# multiplexor_circuit.net
KiCad netlist of a schematic drawn in Altium Designer
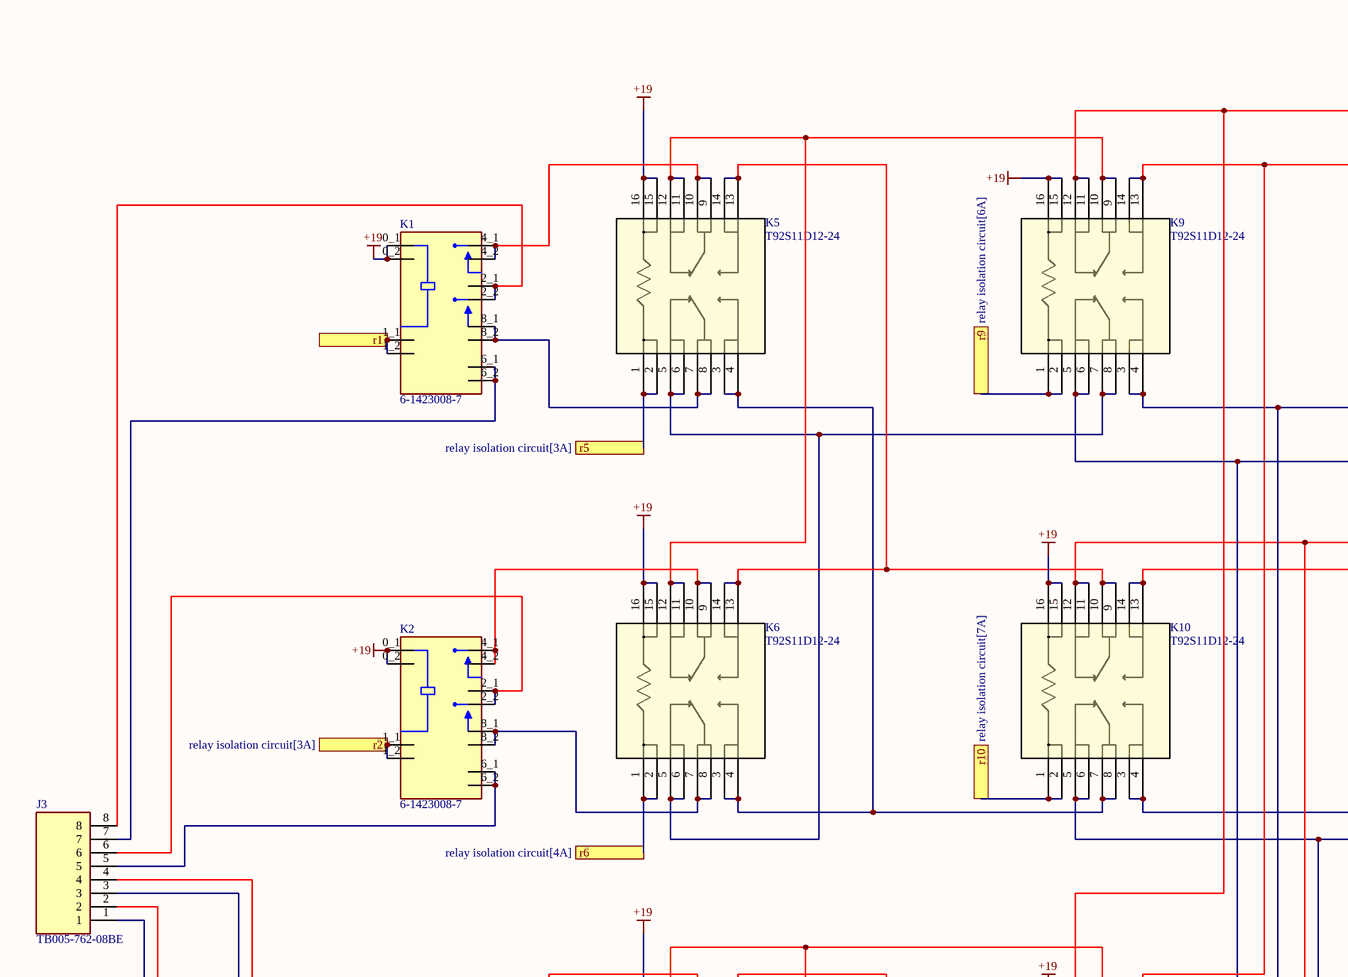
[diagram p0: multiplexor circuit.SchDoc, top left]
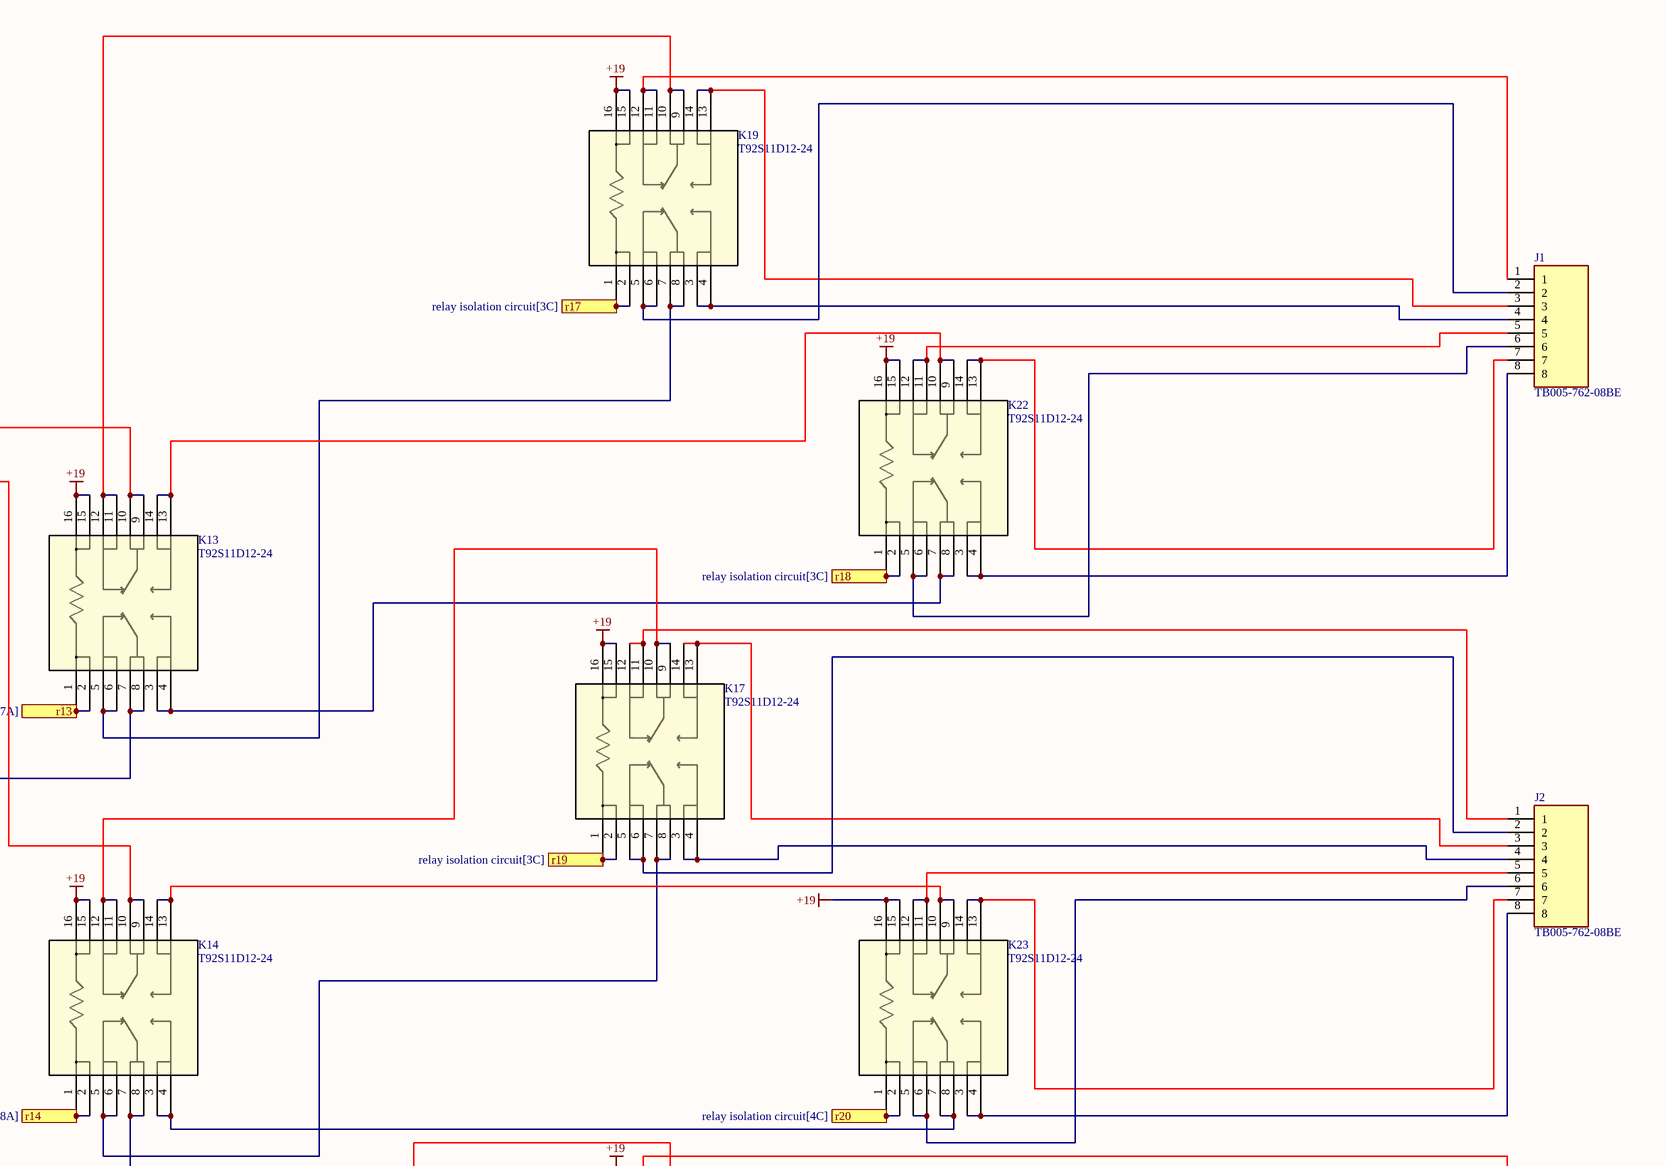
[diagram p1: multiplexor circuit.SchDoc, top right]
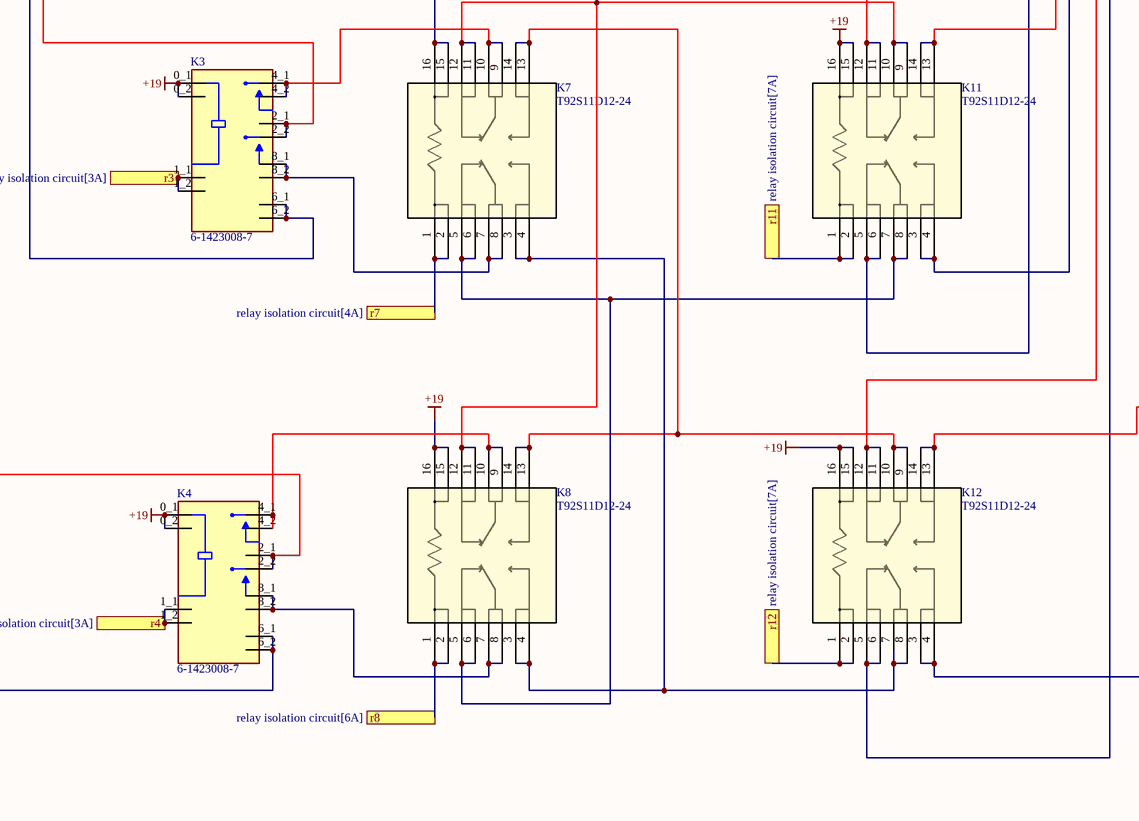
[diagram p2: multiplexor circuit.SchDoc, bottom left]
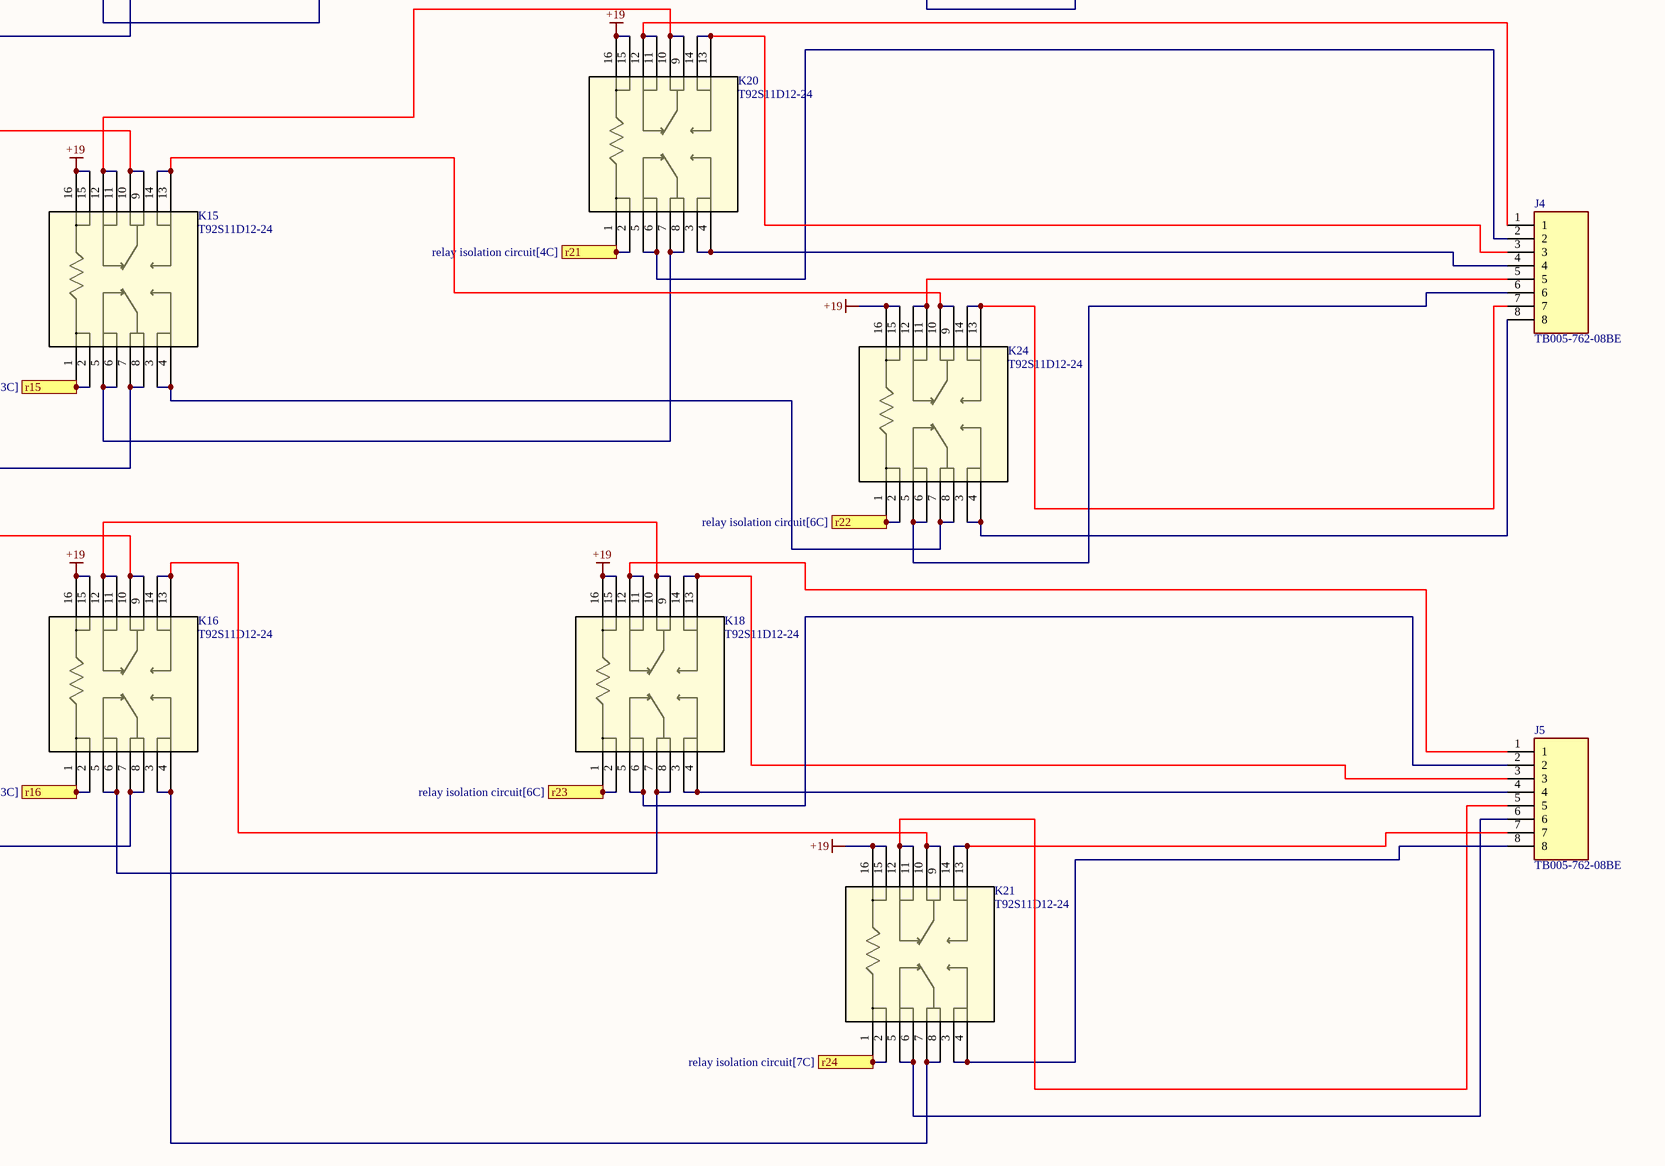
[diagram p3: multiplexor circuit.SchDoc, bottom right]

(export (version "E")
  (design (tool "Eeschema 10.0.6"))
  (components
    (comp (ref "J1")
      (value "TB005-762-08BE")
      (footprint "CUI_TB005-762-08BE")
      (libsource (lib "TB005-762-08BE") (part "TB005-762-08BE"))
    )
    (comp (ref "J2")
      (value "TB005-762-08BE")
      (footprint "CUI_TB005-762-08BE")
      (libsource (lib "TB005-762-08BE") (part "TB005-762-08BE"))
    )
    (comp (ref "J3")
      (value "TB005-762-08BE")
      (footprint "CUI_TB005-762-08BE")
      (libsource (lib "") (part "TB005-762-08BE_1"))
    )
    (comp (ref "J4")
      (value "TB005-762-08BE")
      (footprint "CUI_TB005-762-08BE")
      (libsource (lib "TB005-762-08BE") (part "TB005-762-08BE"))
    )
    (comp (ref "J5")
      (value "TB005-762-08BE")
      (footprint "CUI_TB005-762-08BE")
      (libsource (lib "TB005-762-08BE") (part "TB005-762-08BE"))
    )
    (comp (ref "K1")
      (value "6-1423008-7")
      (footprint "RELAY_6-1423008-7")
      (description "General Purpose Relay DPST-NO (2 Form A) 24VDC Coil Through Hole")
      (fields (field (name "MF") "TE Connectivity / P&B"))
      (libsource (lib "6-1423008-7") (part "6-1423008-7"))
    )
    (comp (ref "K2")
      (value "6-1423008-7")
      (footprint "RELAY_6-1423008-7")
      (description "General Purpose Relay DPST-NO (2 Form A) 24VDC Coil Through Hole")
      (fields (field (name "MF") "TE Connectivity / P&B"))
      (libsource (lib "6-1423008-7") (part "6-1423008-7"))
    )
    (comp (ref "K3")
      (value "6-1423008-7")
      (footprint "RELAY_6-1423008-7")
      (description "General Purpose Relay DPST-NO (2 Form A) 24VDC Coil Through Hole")
      (fields (field (name "MF") "TE Connectivity / P&B"))
      (libsource (lib "6-1423008-7") (part "6-1423008-7"))
    )
    (comp (ref "K4")
      (value "6-1423008-7")
      (footprint "RELAY_6-1423008-7")
      (description "General Purpose Relay DPST-NO (2 Form A) 24VDC Coil Through Hole")
      (fields (field (name "MF") "TE Connectivity / P&B"))
      (libsource (lib "6-1423008-7") (part "6-1423008-7"))
    )
    (comp (ref "K5")
      (value "T92S11D12-24")
      (footprint "T92S11D12-24_TEC-corrected")
      (description "No Description Available")
      (fields (field (name "COPYRIGHT") "Copyright (C) 2022 Ultra Librarian. All rights reserved."))
      (libsource (lib "multiplexorparts") (part "T92S11D12-24"))
    )
    (comp (ref "K6")
      (value "T92S11D12-24")
      (footprint "T92S11D12-24_TEC-corrected")
      (description "No Description Available")
      (fields (field (name "COPYRIGHT") "Copyright (C) 2022 Ultra Librarian. All rights reserved."))
      (libsource (lib "multiplexorparts") (part "T92S11D12-24"))
    )
    (comp (ref "K7")
      (value "T92S11D12-24")
      (footprint "T92S11D12-24_TEC-corrected")
      (description "No Description Available")
      (fields (field (name "COPYRIGHT") "Copyright (C) 2022 Ultra Librarian. All rights reserved."))
      (libsource (lib "multiplexorparts") (part "T92S11D12-24"))
    )
    (comp (ref "K8")
      (value "T92S11D12-24")
      (footprint "T92S11D12-24_TEC-corrected")
      (description "No Description Available")
      (fields (field (name "COPYRIGHT") "Copyright (C) 2022 Ultra Librarian. All rights reserved."))
      (libsource (lib "multiplexorparts") (part "T92S11D12-24"))
    )
    (comp (ref "K9")
      (value "T92S11D12-24")
      (footprint "T92S11D12-24_TEC-corrected")
      (description "No Description Available")
      (fields (field (name "COPYRIGHT") "Copyright (C) 2022 Ultra Librarian. All rights reserved."))
      (libsource (lib "multiplexorparts") (part "T92S11D12-24"))
    )
    (comp (ref "K10")
      (value "T92S11D12-24")
      (footprint "T92S11D12-24_TEC-corrected")
      (description "No Description Available")
      (fields (field (name "COPYRIGHT") "Copyright (C) 2022 Ultra Librarian. All rights reserved."))
      (libsource (lib "multiplexorparts") (part "T92S11D12-24"))
    )
    (comp (ref "K11")
      (value "T92S11D12-24")
      (footprint "T92S11D12-24_TEC-corrected")
      (description "No Description Available")
      (fields (field (name "COPYRIGHT") "Copyright (C) 2022 Ultra Librarian. All rights reserved."))
      (libsource (lib "multiplexorparts") (part "T92S11D12-24"))
    )
    (comp (ref "K12")
      (value "T92S11D12-24")
      (footprint "T92S11D12-24_TEC-corrected")
      (description "No Description Available")
      (fields (field (name "COPYRIGHT") "Copyright (C) 2022 Ultra Librarian. All rights reserved."))
      (libsource (lib "multiplexorparts") (part "T92S11D12-24"))
    )
    (comp (ref "K13")
      (value "T92S11D12-24")
      (footprint "T92S11D12-24_TEC-corrected")
      (description "No Description Available")
      (fields (field (name "COPYRIGHT") "Copyright (C) 2022 Ultra Librarian. All rights reserved."))
      (libsource (lib "multiplexorparts") (part "T92S11D12-24"))
    )
    (comp (ref "K14")
      (value "T92S11D12-24")
      (footprint "T92S11D12-24_TEC-corrected")
      (description "No Description Available")
      (fields (field (name "COPYRIGHT") "Copyright (C) 2022 Ultra Librarian. All rights reserved."))
      (libsource (lib "multiplexorparts") (part "T92S11D12-24"))
    )
    (comp (ref "K15")
      (value "T92S11D12-24")
      (footprint "T92S11D12-24_TEC-corrected")
      (description "No Description Available")
      (fields (field (name "COPYRIGHT") "Copyright (C) 2022 Ultra Librarian. All rights reserved."))
      (libsource (lib "multiplexorparts") (part "T92S11D12-24"))
    )
    (comp (ref "K16")
      (value "T92S11D12-24")
      (footprint "T92S11D12-24_TEC-corrected")
      (description "No Description Available")
      (fields (field (name "COPYRIGHT") "Copyright (C) 2022 Ultra Librarian. All rights reserved."))
      (libsource (lib "multiplexorparts") (part "T92S11D12-24"))
    )
    (comp (ref "K17")
      (value "T92S11D12-24")
      (footprint "T92S11D12-24_TEC-corrected")
      (description "No Description Available")
      (fields (field (name "COPYRIGHT") "Copyright (C) 2022 Ultra Librarian. All rights reserved."))
      (libsource (lib "multiplexorparts") (part "T92S11D12-24"))
    )
    (comp (ref "K18")
      (value "T92S11D12-24")
      (footprint "T92S11D12-24_TEC-corrected")
      (description "No Description Available")
      (fields (field (name "COPYRIGHT") "Copyright (C) 2022 Ultra Librarian. All rights reserved."))
      (libsource (lib "multiplexorparts") (part "T92S11D12-24"))
    )
    (comp (ref "K19")
      (value "T92S11D12-24")
      (footprint "T92S11D12-24_TEC-corrected")
      (description "No Description Available")
      (fields (field (name "COPYRIGHT") "Copyright (C) 2022 Ultra Librarian. All rights reserved."))
      (libsource (lib "multiplexorparts") (part "T92S11D12-24"))
    )
    (comp (ref "K20")
      (value "T92S11D12-24")
      (footprint "T92S11D12-24_TEC-corrected")
      (description "No Description Available")
      (fields (field (name "COPYRIGHT") "Copyright (C) 2022 Ultra Librarian. All rights reserved."))
      (libsource (lib "multiplexorparts") (part "T92S11D12-24"))
    )
    (comp (ref "K21")
      (value "T92S11D12-24")
      (footprint "T92S11D12-24_TEC-corrected")
      (description "No Description Available")
      (fields (field (name "COPYRIGHT") "Copyright (C) 2022 Ultra Librarian. All rights reserved."))
      (libsource (lib "multiplexorparts") (part "T92S11D12-24"))
    )
    (comp (ref "K22")
      (value "T92S11D12-24")
      (footprint "T92S11D12-24_TEC-corrected")
      (description "No Description Available")
      (fields (field (name "COPYRIGHT") "Copyright (C) 2022 Ultra Librarian. All rights reserved."))
      (libsource (lib "multiplexorparts") (part "T92S11D12-24"))
    )
    (comp (ref "K23")
      (value "T92S11D12-24")
      (footprint "T92S11D12-24_TEC-corrected")
      (description "No Description Available")
      (fields (field (name "COPYRIGHT") "Copyright (C) 2022 Ultra Librarian. All rights reserved."))
      (libsource (lib "multiplexorparts") (part "T92S11D12-24"))
    )
    (comp (ref "K24")
      (value "T92S11D12-24")
      (footprint "T92S11D12-24_TEC-corrected")
      (description "No Description Available")
      (fields (field (name "COPYRIGHT") "Copyright (C) 2022 Ultra Librarian. All rights reserved."))
      (libsource (lib "multiplexorparts") (part "T92S11D12-24"))
    )
  )
  (nets
    (net (code "1") (name "+19") (class "Default")
      (node (ref "K1") (pin "0_1") (pinfunction "COIL1_0_1") (pintype "passive"))
      (node (ref "K1") (pin "0_2") (pinfunction "COIL1_0_2") (pintype "passive"))
      (node (ref "K10") (pin "15") (pinfunction "15_15") (pintype "passive"))
      (node (ref "K10") (pin "16") (pinfunction "16_16") (pintype "passive"))
      (node (ref "K11") (pin "15") (pinfunction "15_15") (pintype "passive"))
      (node (ref "K11") (pin "16") (pinfunction "16_16") (pintype "passive"))
      (node (ref "K12") (pin "15") (pinfunction "15_15") (pintype "passive"))
      (node (ref "K12") (pin "16") (pinfunction "16_16") (pintype "passive"))
      (node (ref "K13") (pin "15") (pinfunction "15_15") (pintype "passive"))
      (node (ref "K13") (pin "16") (pinfunction "16_16") (pintype "passive"))
      (node (ref "K14") (pin "15") (pinfunction "15_15") (pintype "passive"))
      (node (ref "K14") (pin "16") (pinfunction "16_16") (pintype "passive"))
      (node (ref "K15") (pin "15") (pinfunction "15_15") (pintype "passive"))
      (node (ref "K15") (pin "16") (pinfunction "16_16") (pintype "passive"))
      (node (ref "K16") (pin "15") (pinfunction "15_15") (pintype "passive"))
      (node (ref "K16") (pin "16") (pinfunction "16_16") (pintype "passive"))
      (node (ref "K17") (pin "15") (pinfunction "15_15") (pintype "passive"))
      (node (ref "K17") (pin "16") (pinfunction "16_16") (pintype "passive"))
      (node (ref "K18") (pin "15") (pinfunction "15_15") (pintype "passive"))
      (node (ref "K18") (pin "16") (pinfunction "16_16") (pintype "passive"))
      (node (ref "K19") (pin "15") (pinfunction "15_15") (pintype "passive"))
      (node (ref "K19") (pin "16") (pinfunction "16_16") (pintype "passive"))
      (node (ref "K2") (pin "0_1") (pinfunction "COIL1_0_1") (pintype "passive"))
      (node (ref "K2") (pin "0_2") (pinfunction "COIL1_0_2") (pintype "passive"))
      (node (ref "K20") (pin "15") (pinfunction "15_15") (pintype "passive"))
      (node (ref "K20") (pin "16") (pinfunction "16_16") (pintype "passive"))
      (node (ref "K21") (pin "15") (pinfunction "15_15") (pintype "passive"))
      (node (ref "K21") (pin "16") (pinfunction "16_16") (pintype "passive"))
      (node (ref "K22") (pin "15") (pinfunction "15_15") (pintype "passive"))
      (node (ref "K22") (pin "16") (pinfunction "16_16") (pintype "passive"))
      (node (ref "K23") (pin "15") (pinfunction "15_15") (pintype "passive"))
      (node (ref "K23") (pin "16") (pinfunction "16_16") (pintype "passive"))
      (node (ref "K24") (pin "15") (pinfunction "15_15") (pintype "passive"))
      (node (ref "K24") (pin "16") (pinfunction "16_16") (pintype "passive"))
      (node (ref "K3") (pin "0_1") (pinfunction "COIL1_0_1") (pintype "passive"))
      (node (ref "K3") (pin "0_2") (pinfunction "COIL1_0_2") (pintype "passive"))
      (node (ref "K4") (pin "0_1") (pinfunction "COIL1_0_1") (pintype "passive"))
      (node (ref "K4") (pin "0_2") (pinfunction "COIL1_0_2") (pintype "passive"))
      (node (ref "K5") (pin "15") (pinfunction "15_15") (pintype "passive"))
      (node (ref "K5") (pin "16") (pinfunction "16_16") (pintype "passive"))
      (node (ref "K6") (pin "15") (pinfunction "15_15") (pintype "passive"))
      (node (ref "K6") (pin "16") (pinfunction "16_16") (pintype "passive"))
      (node (ref "K7") (pin "15") (pinfunction "15_15") (pintype "passive"))
      (node (ref "K7") (pin "16") (pinfunction "16_16") (pintype "passive"))
      (node (ref "K8") (pin "15") (pinfunction "15_15") (pintype "passive"))
      (node (ref "K8") (pin "16") (pinfunction "16_16") (pintype "passive"))
      (node (ref "K9") (pin "15") (pinfunction "15_15") (pintype "passive"))
      (node (ref "K9") (pin "16") (pinfunction "16_16") (pintype "passive"))
    )
    (net (code "2") (name "/r1") (class "Default")
      (node (ref "K1") (pin "1_1") (pinfunction "COIL2_1_1") (pintype "passive"))
      (node (ref "K1") (pin "1_2") (pinfunction "COIL2_1_2") (pintype "passive"))
    )
    (net (code "3") (name "/r2") (class "Default")
      (node (ref "K2") (pin "1_1") (pinfunction "COIL2_1_1") (pintype "passive"))
      (node (ref "K2") (pin "1_2") (pinfunction "COIL2_1_2") (pintype "passive"))
    )
    (net (code "4") (name "/r3") (class "Default")
      (node (ref "K3") (pin "1_1") (pinfunction "COIL2_1_1") (pintype "passive"))
      (node (ref "K3") (pin "1_2") (pinfunction "COIL2_1_2") (pintype "passive"))
    )
    (net (code "5") (name "/r4") (class "Default")
      (node (ref "K4") (pin "1_1") (pinfunction "COIL2_1_1") (pintype "passive"))
      (node (ref "K4") (pin "1_2") (pinfunction "COIL2_1_2") (pintype "passive"))
    )
    (net (code "6") (name "/r5") (class "Default")
      (node (ref "K5") (pin "1") (pinfunction "1_1") (pintype "passive"))
      (node (ref "K5") (pin "2") (pinfunction "2_2") (pintype "passive"))
    )
    (net (code "7") (name "/r6") (class "Default")
      (node (ref "K6") (pin "1") (pinfunction "1_1") (pintype "passive"))
      (node (ref "K6") (pin "2") (pinfunction "2_2") (pintype "passive"))
    )
    (net (code "8") (name "/r7") (class "Default")
      (node (ref "K7") (pin "1") (pinfunction "1_1") (pintype "passive"))
      (node (ref "K7") (pin "2") (pinfunction "2_2") (pintype "passive"))
    )
    (net (code "9") (name "/r8") (class "Default")
      (node (ref "K8") (pin "1") (pinfunction "1_1") (pintype "passive"))
      (node (ref "K8") (pin "2") (pinfunction "2_2") (pintype "passive"))
    )
    (net (code "10") (name "/r9") (class "Default")
      (node (ref "K9") (pin "1") (pinfunction "1_1") (pintype "passive"))
      (node (ref "K9") (pin "2") (pinfunction "2_2") (pintype "passive"))
    )
    (net (code "11") (name "/r10") (class "Default")
      (node (ref "K10") (pin "1") (pinfunction "1_1") (pintype "passive"))
      (node (ref "K10") (pin "2") (pinfunction "2_2") (pintype "passive"))
    )
    (net (code "12") (name "/r11") (class "Default")
      (node (ref "K11") (pin "1") (pinfunction "1_1") (pintype "passive"))
      (node (ref "K11") (pin "2") (pinfunction "2_2") (pintype "passive"))
    )
    (net (code "13") (name "/r12") (class "Default")
      (node (ref "K12") (pin "1") (pinfunction "1_1") (pintype "passive"))
      (node (ref "K12") (pin "2") (pinfunction "2_2") (pintype "passive"))
    )
    (net (code "14") (name "/r13") (class "Default")
      (node (ref "K13") (pin "1") (pinfunction "1_1") (pintype "passive"))
      (node (ref "K13") (pin "2") (pinfunction "2_2") (pintype "passive"))
    )
    (net (code "15") (name "/r14") (class "Default")
      (node (ref "K14") (pin "1") (pinfunction "1_1") (pintype "passive"))
      (node (ref "K14") (pin "2") (pinfunction "2_2") (pintype "passive"))
    )
    (net (code "16") (name "/r15") (class "Default")
      (node (ref "K15") (pin "1") (pinfunction "1_1") (pintype "passive"))
      (node (ref "K15") (pin "2") (pinfunction "2_2") (pintype "passive"))
    )
    (net (code "17") (name "/r16") (class "Default")
      (node (ref "K16") (pin "1") (pinfunction "1_1") (pintype "passive"))
      (node (ref "K16") (pin "2") (pinfunction "2_2") (pintype "passive"))
    )
    (net (code "18") (name "/r17") (class "Default")
      (node (ref "K19") (pin "1") (pinfunction "1_1") (pintype "passive"))
      (node (ref "K19") (pin "2") (pinfunction "2_2") (pintype "passive"))
    )
    (net (code "19") (name "/r18") (class "Default")
      (node (ref "K22") (pin "1") (pinfunction "1_1") (pintype "passive"))
      (node (ref "K22") (pin "2") (pinfunction "2_2") (pintype "passive"))
    )
    (net (code "20") (name "/r19") (class "Default")
      (node (ref "K17") (pin "1") (pinfunction "1_1") (pintype "passive"))
      (node (ref "K17") (pin "2") (pinfunction "2_2") (pintype "passive"))
    )
    (net (code "21") (name "/r20") (class "Default")
      (node (ref "K23") (pin "1") (pinfunction "1_1") (pintype "passive"))
      (node (ref "K23") (pin "2") (pinfunction "2_2") (pintype "passive"))
    )
    (net (code "22") (name "/r21") (class "Default")
      (node (ref "K20") (pin "1") (pinfunction "1_1") (pintype "passive"))
      (node (ref "K20") (pin "2") (pinfunction "2_2") (pintype "passive"))
    )
    (net (code "23") (name "/r22") (class "Default")
      (node (ref "K24") (pin "1") (pinfunction "1_1") (pintype "passive"))
      (node (ref "K24") (pin "2") (pinfunction "2_2") (pintype "passive"))
    )
    (net (code "24") (name "/r23") (class "Default")
      (node (ref "K18") (pin "1") (pinfunction "1_1") (pintype "passive"))
      (node (ref "K18") (pin "2") (pinfunction "2_2") (pintype "passive"))
    )
    (net (code "25") (name "/r24") (class "Default")
      (node (ref "K21") (pin "1") (pinfunction "1_1") (pintype "passive"))
      (node (ref "K21") (pin "2") (pinfunction "2_2") (pintype "passive"))
    )
    (net (code "26") (name "Net-(J1-Pad1)") (class "Default")
      (node (ref "J1") (pin "1") (pinfunction "1_1") (pintype "passive"))
      (node (ref "K19") (pin "11") (pinfunction "11_11") (pintype "passive"))
      (node (ref "K19") (pin "12") (pinfunction "12_12") (pintype "passive"))
    )
    (net (code "27") (name "Net-(J1-Pad2)") (class "Default")
      (node (ref "J1") (pin "2") (pinfunction "2_2") (pintype "passive"))
      (node (ref "K19") (pin "5") (pinfunction "5_5") (pintype "passive"))
      (node (ref "K19") (pin "6") (pinfunction "6_6") (pintype "passive"))
    )
    (net (code "28") (name "Net-(J1-Pad3)") (class "Default")
      (node (ref "J1") (pin "3") (pinfunction "3_3") (pintype "passive"))
      (node (ref "K19") (pin "13") (pinfunction "13_13") (pintype "passive"))
      (node (ref "K19") (pin "14") (pinfunction "14_14") (pintype "passive"))
    )
    (net (code "29") (name "Net-(J1-Pad4)") (class "Default")
      (node (ref "J1") (pin "4") (pinfunction "4_4") (pintype "passive"))
      (node (ref "K19") (pin "3") (pinfunction "3_3") (pintype "passive"))
      (node (ref "K19") (pin "4") (pinfunction "4_4") (pintype "passive"))
    )
    (net (code "30") (name "Net-(J1-Pad5)") (class "Default")
      (node (ref "J1") (pin "5") (pinfunction "5_5") (pintype "passive"))
      (node (ref "K22") (pin "11") (pinfunction "11_11") (pintype "passive"))
      (node (ref "K22") (pin "12") (pinfunction "12_12") (pintype "passive"))
    )
    (net (code "31") (name "Net-(J1-Pad6)") (class "Default")
      (node (ref "J1") (pin "6") (pinfunction "6_6") (pintype "passive"))
      (node (ref "K22") (pin "5") (pinfunction "5_5") (pintype "passive"))
      (node (ref "K22") (pin "6") (pinfunction "6_6") (pintype "passive"))
    )
    (net (code "32") (name "Net-(J1-Pad7)") (class "Default")
      (node (ref "J1") (pin "7") (pinfunction "7_7") (pintype "passive"))
      (node (ref "K22") (pin "13") (pinfunction "13_13") (pintype "passive"))
      (node (ref "K22") (pin "14") (pinfunction "14_14") (pintype "passive"))
    )
    (net (code "33") (name "Net-(J1-Pad8)") (class "Default")
      (node (ref "J1") (pin "8") (pinfunction "8_8") (pintype "passive"))
      (node (ref "K22") (pin "3") (pinfunction "3_3") (pintype "passive"))
      (node (ref "K22") (pin "4") (pinfunction "4_4") (pintype "passive"))
    )
    (net (code "34") (name "Net-(J2-Pad1)") (class "Default")
      (node (ref "J2") (pin "1") (pinfunction "1_1") (pintype "passive"))
      (node (ref "K17") (pin "11") (pinfunction "11_11") (pintype "passive"))
      (node (ref "K17") (pin "12") (pinfunction "12_12") (pintype "passive"))
    )
    (net (code "35") (name "Net-(J2-Pad2)") (class "Default")
      (node (ref "J2") (pin "2") (pinfunction "2_2") (pintype "passive"))
      (node (ref "K17") (pin "5") (pinfunction "5_5") (pintype "passive"))
      (node (ref "K17") (pin "6") (pinfunction "6_6") (pintype "passive"))
    )
    (net (code "36") (name "Net-(J2-Pad3)") (class "Default")
      (node (ref "J2") (pin "3") (pinfunction "3_3") (pintype "passive"))
      (node (ref "K17") (pin "13") (pinfunction "13_13") (pintype "passive"))
      (node (ref "K17") (pin "14") (pinfunction "14_14") (pintype "passive"))
    )
    (net (code "37") (name "Net-(J2-Pad4)") (class "Default")
      (node (ref "J2") (pin "4") (pinfunction "4_4") (pintype "passive"))
      (node (ref "K17") (pin "3") (pinfunction "3_3") (pintype "passive"))
      (node (ref "K17") (pin "4") (pinfunction "4_4") (pintype "passive"))
    )
    (net (code "38") (name "Net-(J2-Pad5)") (class "Default")
      (node (ref "J2") (pin "5") (pinfunction "5_5") (pintype "passive"))
      (node (ref "K23") (pin "11") (pinfunction "11_11") (pintype "passive"))
      (node (ref "K23") (pin "12") (pinfunction "12_12") (pintype "passive"))
    )
    (net (code "39") (name "Net-(J2-Pad6)") (class "Default")
      (node (ref "J2") (pin "6") (pinfunction "6_6") (pintype "passive"))
      (node (ref "K23") (pin "5") (pinfunction "5_5") (pintype "passive"))
      (node (ref "K23") (pin "6") (pinfunction "6_6") (pintype "passive"))
    )
    (net (code "40") (name "Net-(J2-Pad7)") (class "Default")
      (node (ref "J2") (pin "7") (pinfunction "7_7") (pintype "passive"))
      (node (ref "K23") (pin "13") (pinfunction "13_13") (pintype "passive"))
      (node (ref "K23") (pin "14") (pinfunction "14_14") (pintype "passive"))
    )
    (net (code "41") (name "Net-(J2-Pad8)") (class "Default")
      (node (ref "J2") (pin "8") (pinfunction "8_8") (pintype "passive"))
      (node (ref "K23") (pin "3") (pinfunction "3_3") (pintype "passive"))
      (node (ref "K23") (pin "4") (pinfunction "4_4") (pintype "passive"))
    )
    (net (code "42") (name "Net-(J3-Pad1)") (class "Default")
      (node (ref "J3") (pin "1") (pinfunction "1_1") (pintype "passive"))
      (node (ref "K4") (pin "6_1") (pinfunction "NO2_6_1") (pintype "passive"))
      (node (ref "K4") (pin "6_2") (pinfunction "NO2_6_2") (pintype "passive"))
    )
    (net (code "43") (name "Net-(J3-Pad2)") (class "Default")
      (node (ref "J3") (pin "2") (pinfunction "2_2") (pintype "passive"))
      (node (ref "K4") (pin "2_1") (pinfunction "NO1_2_1") (pintype "passive"))
      (node (ref "K4") (pin "2_2") (pinfunction "NO1_2_2") (pintype "passive"))
    )
    (net (code "44") (name "Net-(J3-Pad3)") (class "Default")
      (node (ref "J3") (pin "3") (pinfunction "3_3") (pintype "passive"))
      (node (ref "K3") (pin "6_1") (pinfunction "NO2_6_1") (pintype "passive"))
      (node (ref "K3") (pin "6_2") (pinfunction "NO2_6_2") (pintype "passive"))
    )
    (net (code "45") (name "Net-(J3-Pad4)") (class "Default")
      (node (ref "J3") (pin "4") (pinfunction "4_4") (pintype "passive"))
      (node (ref "K3") (pin "2_1") (pinfunction "NO1_2_1") (pintype "passive"))
      (node (ref "K3") (pin "2_2") (pinfunction "NO1_2_2") (pintype "passive"))
    )
    (net (code "46") (name "Net-(J3-Pad5)") (class "Default")
      (node (ref "J3") (pin "5") (pinfunction "5_5") (pintype "passive"))
      (node (ref "K2") (pin "6_1") (pinfunction "NO2_6_1") (pintype "passive"))
      (node (ref "K2") (pin "6_2") (pinfunction "NO2_6_2") (pintype "passive"))
    )
    (net (code "47") (name "Net-(J3-Pad6)") (class "Default")
      (node (ref "J3") (pin "6") (pinfunction "6_6") (pintype "passive"))
      (node (ref "K2") (pin "2_1") (pinfunction "NO1_2_1") (pintype "passive"))
      (node (ref "K2") (pin "2_2") (pinfunction "NO1_2_2") (pintype "passive"))
    )
    (net (code "48") (name "Net-(J3-Pad7)") (class "Default")
      (node (ref "J3") (pin "7") (pinfunction "7_7") (pintype "passive"))
      (node (ref "K1") (pin "6_1") (pinfunction "NO2_6_1") (pintype "passive"))
      (node (ref "K1") (pin "6_2") (pinfunction "NO2_6_2") (pintype "passive"))
    )
    (net (code "49") (name "Net-(J3-Pad8)") (class "Default")
      (node (ref "J3") (pin "8") (pinfunction "8_8") (pintype "passive"))
      (node (ref "K1") (pin "2_1") (pinfunction "NO1_2_1") (pintype "passive"))
      (node (ref "K1") (pin "2_2") (pinfunction "NO1_2_2") (pintype "passive"))
    )
    (net (code "50") (name "Net-(J4-Pad1)") (class "Default")
      (node (ref "J4") (pin "1") (pinfunction "1_1") (pintype "passive"))
      (node (ref "K20") (pin "11") (pinfunction "11_11") (pintype "passive"))
      (node (ref "K20") (pin "12") (pinfunction "12_12") (pintype "passive"))
    )
    (net (code "51") (name "Net-(J4-Pad2)") (class "Default")
      (node (ref "J4") (pin "2") (pinfunction "2_2") (pintype "passive"))
      (node (ref "K20") (pin "5") (pinfunction "5_5") (pintype "passive"))
      (node (ref "K20") (pin "6") (pinfunction "6_6") (pintype "passive"))
    )
    (net (code "52") (name "Net-(J4-Pad3)") (class "Default")
      (node (ref "J4") (pin "3") (pinfunction "3_3") (pintype "passive"))
      (node (ref "K20") (pin "13") (pinfunction "13_13") (pintype "passive"))
      (node (ref "K20") (pin "14") (pinfunction "14_14") (pintype "passive"))
    )
    (net (code "53") (name "Net-(J4-Pad4)") (class "Default")
      (node (ref "J4") (pin "4") (pinfunction "4_4") (pintype "passive"))
      (node (ref "K20") (pin "3") (pinfunction "3_3") (pintype "passive"))
      (node (ref "K20") (pin "4") (pinfunction "4_4") (pintype "passive"))
    )
    (net (code "54") (name "Net-(J4-Pad5)") (class "Default")
      (node (ref "J4") (pin "5") (pinfunction "5_5") (pintype "passive"))
      (node (ref "K24") (pin "11") (pinfunction "11_11") (pintype "passive"))
      (node (ref "K24") (pin "12") (pinfunction "12_12") (pintype "passive"))
    )
    (net (code "55") (name "Net-(J4-Pad6)") (class "Default")
      (node (ref "J4") (pin "6") (pinfunction "6_6") (pintype "passive"))
      (node (ref "K24") (pin "5") (pinfunction "5_5") (pintype "passive"))
      (node (ref "K24") (pin "6") (pinfunction "6_6") (pintype "passive"))
    )
    (net (code "56") (name "Net-(J4-Pad7)") (class "Default")
      (node (ref "J4") (pin "7") (pinfunction "7_7") (pintype "passive"))
      (node (ref "K24") (pin "13") (pinfunction "13_13") (pintype "passive"))
      (node (ref "K24") (pin "14") (pinfunction "14_14") (pintype "passive"))
    )
    (net (code "57") (name "Net-(J4-Pad8)") (class "Default")
      (node (ref "J4") (pin "8") (pinfunction "8_8") (pintype "passive"))
      (node (ref "K24") (pin "3") (pinfunction "3_3") (pintype "passive"))
      (node (ref "K24") (pin "4") (pinfunction "4_4") (pintype "passive"))
    )
    (net (code "58") (name "Net-(J5-Pad1)") (class "Default")
      (node (ref "J5") (pin "1") (pinfunction "1_1") (pintype "passive"))
      (node (ref "K18") (pin "11") (pinfunction "11_11") (pintype "passive"))
      (node (ref "K18") (pin "12") (pinfunction "12_12") (pintype "passive"))
    )
    (net (code "59") (name "Net-(J5-Pad2)") (class "Default")
      (node (ref "J5") (pin "2") (pinfunction "2_2") (pintype "passive"))
      (node (ref "K18") (pin "5") (pinfunction "5_5") (pintype "passive"))
      (node (ref "K18") (pin "6") (pinfunction "6_6") (pintype "passive"))
    )
    (net (code "60") (name "Net-(J5-Pad3)") (class "Default")
      (node (ref "J5") (pin "3") (pinfunction "3_3") (pintype "passive"))
      (node (ref "K18") (pin "13") (pinfunction "13_13") (pintype "passive"))
      (node (ref "K18") (pin "14") (pinfunction "14_14") (pintype "passive"))
    )
    (net (code "61") (name "Net-(J5-Pad4)") (class "Default")
      (node (ref "J5") (pin "4") (pinfunction "4_4") (pintype "passive"))
      (node (ref "K18") (pin "3") (pinfunction "3_3") (pintype "passive"))
      (node (ref "K18") (pin "4") (pinfunction "4_4") (pintype "passive"))
    )
    (net (code "62") (name "Net-(J5-Pad5)") (class "Default")
      (node (ref "J5") (pin "5") (pinfunction "5_5") (pintype "passive"))
      (node (ref "K21") (pin "11") (pinfunction "11_11") (pintype "passive"))
      (node (ref "K21") (pin "12") (pinfunction "12_12") (pintype "passive"))
    )
    (net (code "63") (name "Net-(J5-Pad6)") (class "Default")
      (node (ref "J5") (pin "6") (pinfunction "6_6") (pintype "passive"))
      (node (ref "K21") (pin "5") (pinfunction "5_5") (pintype "passive"))
      (node (ref "K21") (pin "6") (pinfunction "6_6") (pintype "passive"))
    )
    (net (code "64") (name "Net-(J5-Pad7)") (class "Default")
      (node (ref "J5") (pin "7") (pinfunction "7_7") (pintype "passive"))
      (node (ref "K21") (pin "13") (pinfunction "13_13") (pintype "passive"))
      (node (ref "K21") (pin "14") (pinfunction "14_14") (pintype "passive"))
    )
    (net (code "65") (name "Net-(J5-Pad8)") (class "Default")
      (node (ref "J5") (pin "8") (pinfunction "8_8") (pintype "passive"))
      (node (ref "K21") (pin "3") (pinfunction "3_3") (pintype "passive"))
      (node (ref "K21") (pin "4") (pinfunction "4_4") (pintype "passive"))
    )
    (net (code "66") (name "Net-(K1-COM1-Pad4_1)") (class "Default")
      (node (ref "K1") (pin "4_1") (pinfunction "COM1_4_1") (pintype "passive"))
      (node (ref "K1") (pin "4_2") (pinfunction "COM1_4_2") (pintype "passive"))
      (node (ref "K5") (pin "10") (pinfunction "10_10") (pintype "passive"))
      (node (ref "K5") (pin "9") (pinfunction "9_9") (pintype "passive"))
    )
    (net (code "67") (name "Net-(K1-COM2-Pad8_1)") (class "Default")
      (node (ref "K1") (pin "8_1") (pinfunction "COM2_8_1") (pintype "passive"))
      (node (ref "K1") (pin "8_2") (pinfunction "COM2_8_2") (pintype "passive"))
      (node (ref "K5") (pin "7") (pinfunction "7_7") (pintype "passive"))
      (node (ref "K5") (pin "8") (pinfunction "8_8") (pintype "passive"))
    )
    (net (code "68") (name "Net-(K2-COM1-Pad4_1)") (class "Default")
      (node (ref "K2") (pin "4_1") (pinfunction "COM1_4_1") (pintype "passive"))
      (node (ref "K2") (pin "4_2") (pinfunction "COM1_4_2") (pintype "passive"))
      (node (ref "K6") (pin "10") (pinfunction "10_10") (pintype "passive"))
      (node (ref "K6") (pin "9") (pinfunction "9_9") (pintype "passive"))
    )
    (net (code "69") (name "Net-(K2-COM2-Pad8_1)") (class "Default")
      (node (ref "K2") (pin "8_1") (pinfunction "COM2_8_1") (pintype "passive"))
      (node (ref "K2") (pin "8_2") (pinfunction "COM2_8_2") (pintype "passive"))
      (node (ref "K6") (pin "7") (pinfunction "7_7") (pintype "passive"))
      (node (ref "K6") (pin "8") (pinfunction "8_8") (pintype "passive"))
    )
    (net (code "70") (name "Net-(K3-COM1-Pad4_1)") (class "Default")
      (node (ref "K3") (pin "4_1") (pinfunction "COM1_4_1") (pintype "passive"))
      (node (ref "K3") (pin "4_2") (pinfunction "COM1_4_2") (pintype "passive"))
      (node (ref "K7") (pin "10") (pinfunction "10_10") (pintype "passive"))
      (node (ref "K7") (pin "9") (pinfunction "9_9") (pintype "passive"))
    )
    (net (code "71") (name "Net-(K3-COM2-Pad8_1)") (class "Default")
      (node (ref "K3") (pin "8_1") (pinfunction "COM2_8_1") (pintype "passive"))
      (node (ref "K3") (pin "8_2") (pinfunction "COM2_8_2") (pintype "passive"))
      (node (ref "K7") (pin "7") (pinfunction "7_7") (pintype "passive"))
      (node (ref "K7") (pin "8") (pinfunction "8_8") (pintype "passive"))
    )
    (net (code "72") (name "Net-(K4-COM1-Pad4_1)") (class "Default")
      (node (ref "K4") (pin "4_1") (pinfunction "COM1_4_1") (pintype "passive"))
      (node (ref "K4") (pin "4_2") (pinfunction "COM1_4_2") (pintype "passive"))
      (node (ref "K8") (pin "10") (pinfunction "10_10") (pintype "passive"))
      (node (ref "K8") (pin "9") (pinfunction "9_9") (pintype "passive"))
    )
    (net (code "73") (name "Net-(K4-COM2-Pad8_1)") (class "Default")
      (node (ref "K4") (pin "8_1") (pinfunction "COM2_8_1") (pintype "passive"))
      (node (ref "K4") (pin "8_2") (pinfunction "COM2_8_2") (pintype "passive"))
      (node (ref "K8") (pin "7") (pinfunction "7_7") (pintype "passive"))
      (node (ref "K8") (pin "8") (pinfunction "8_8") (pintype "passive"))
    )
    (net (code "74") (name "Net-(K5-Pad5)") (class "Default")
      (node (ref "K5") (pin "5") (pinfunction "5_5") (pintype "passive"))
      (node (ref "K5") (pin "6") (pinfunction "6_6") (pintype "passive"))
      (node (ref "K6") (pin "5") (pinfunction "5_5") (pintype "passive"))
      (node (ref "K6") (pin "6") (pinfunction "6_6") (pintype "passive"))
      (node (ref "K9") (pin "7") (pinfunction "7_7") (pintype "passive"))
      (node (ref "K9") (pin "8") (pinfunction "8_8") (pintype "passive"))
    )
    (net (code "75") (name "Net-(K5-Pad11)") (class "Default")
      (node (ref "K5") (pin "11") (pinfunction "11_11") (pintype "passive"))
      (node (ref "K5") (pin "12") (pinfunction "12_12") (pintype "passive"))
      (node (ref "K6") (pin "11") (pinfunction "11_11") (pintype "passive"))
      (node (ref "K6") (pin "12") (pinfunction "12_12") (pintype "passive"))
      (node (ref "K9") (pin "10") (pinfunction "10_10") (pintype "passive"))
      (node (ref "K9") (pin "9") (pinfunction "9_9") (pintype "passive"))
    )
    (net (code "76") (name "Net-(K10-Pad3)") (class "Default")
      (node (ref "K10") (pin "3") (pinfunction "3_3") (pintype "passive"))
      (node (ref "K10") (pin "4") (pinfunction "4_4") (pintype "passive"))
      (node (ref "K12") (pin "3") (pinfunction "3_3") (pintype "passive"))
      (node (ref "K12") (pin "4") (pinfunction "4_4") (pintype "passive"))
      (node (ref "K16") (pin "7") (pinfunction "7_7") (pintype "passive"))
      (node (ref "K16") (pin "8") (pinfunction "8_8") (pintype "passive"))
    )
    (net (code "77") (name "Net-(K10-Pad5)") (class "Default")
      (node (ref "K10") (pin "5") (pinfunction "5_5") (pintype "passive"))
      (node (ref "K10") (pin "6") (pinfunction "6_6") (pintype "passive"))
      (node (ref "K12") (pin "5") (pinfunction "5_5") (pintype "passive"))
      (node (ref "K12") (pin "6") (pinfunction "6_6") (pintype "passive"))
      (node (ref "K15") (pin "7") (pinfunction "7_7") (pintype "passive"))
      (node (ref "K15") (pin "8") (pinfunction "8_8") (pintype "passive"))
    )
    (net (code "78") (name "Net-(K10-Pad7)") (class "Default")
      (node (ref "K10") (pin "7") (pinfunction "7_7") (pintype "passive"))
      (node (ref "K10") (pin "8") (pinfunction "8_8") (pintype "passive"))
      (node (ref "K5") (pin "3") (pinfunction "3_3") (pintype "passive"))
      (node (ref "K5") (pin "4") (pinfunction "4_4") (pintype "passive"))
      (node (ref "K6") (pin "3") (pinfunction "3_3") (pintype "passive"))
      (node (ref "K6") (pin "4") (pinfunction "4_4") (pintype "passive"))
    )
    (net (code "79") (name "Net-(K10-Pad10)") (class "Default")
      (node (ref "K10") (pin "10") (pinfunction "10_10") (pintype "passive"))
      (node (ref "K10") (pin "9") (pinfunction "9_9") (pintype "passive"))
      (node (ref "K5") (pin "13") (pinfunction "13_13") (pintype "passive"))
      (node (ref "K5") (pin "14") (pinfunction "14_14") (pintype "passive"))
      (node (ref "K6") (pin "13") (pinfunction "13_13") (pintype "passive"))
      (node (ref "K6") (pin "14") (pinfunction "14_14") (pintype "passive"))
    )
    (net (code "80") (name "Net-(K10-Pad11)") (class "Default")
      (node (ref "K10") (pin "11") (pinfunction "11_11") (pintype "passive"))
      (node (ref "K10") (pin "12") (pinfunction "12_12") (pintype "passive"))
      (node (ref "K12") (pin "11") (pinfunction "11_11") (pintype "passive"))
      (node (ref "K12") (pin "12") (pinfunction "12_12") (pintype "passive"))
      (node (ref "K15") (pin "10") (pinfunction "10_10") (pintype "passive"))
      (node (ref "K15") (pin "9") (pinfunction "9_9") (pintype "passive"))
    )
    (net (code "81") (name "Net-(K10-Pad13)") (class "Default")
      (node (ref "K10") (pin "13") (pinfunction "13_13") (pintype "passive"))
      (node (ref "K10") (pin "14") (pinfunction "14_14") (pintype "passive"))
      (node (ref "K12") (pin "13") (pinfunction "13_13") (pintype "passive"))
      (node (ref "K12") (pin "14") (pinfunction "14_14") (pintype "passive"))
      (node (ref "K16") (pin "10") (pinfunction "10_10") (pintype "passive"))
      (node (ref "K16") (pin "9") (pinfunction "9_9") (pintype "passive"))
    )
    (net (code "82") (name "Net-(K11-Pad3)") (class "Default")
      (node (ref "K11") (pin "3") (pinfunction "3_3") (pintype "passive"))
      (node (ref "K11") (pin "4") (pinfunction "4_4") (pintype "passive"))
      (node (ref "K14") (pin "7") (pinfunction "7_7") (pintype "passive"))
      (node (ref "K14") (pin "8") (pinfunction "8_8") (pintype "passive"))
      (node (ref "K9") (pin "3") (pinfunction "3_3") (pintype "passive"))
      (node (ref "K9") (pin "4") (pinfunction "4_4") (pintype "passive"))
    )
    (net (code "83") (name "Net-(K11-Pad5)") (class "Default")
      (node (ref "K11") (pin "5") (pinfunction "5_5") (pintype "passive"))
      (node (ref "K11") (pin "6") (pinfunction "6_6") (pintype "passive"))
      (node (ref "K13") (pin "7") (pinfunction "7_7") (pintype "passive"))
      (node (ref "K13") (pin "8") (pinfunction "8_8") (pintype "passive"))
      (node (ref "K9") (pin "5") (pinfunction "5_5") (pintype "passive"))
      (node (ref "K9") (pin "6") (pinfunction "6_6") (pintype "passive"))
    )
    (net (code "84") (name "Net-(K11-Pad7)") (class "Default")
      (node (ref "K11") (pin "7") (pinfunction "7_7") (pintype "passive"))
      (node (ref "K11") (pin "8") (pinfunction "8_8") (pintype "passive"))
      (node (ref "K7") (pin "5") (pinfunction "5_5") (pintype "passive"))
      (node (ref "K7") (pin "6") (pinfunction "6_6") (pintype "passive"))
      (node (ref "K8") (pin "5") (pinfunction "5_5") (pintype "passive"))
      (node (ref "K8") (pin "6") (pinfunction "6_6") (pintype "passive"))
    )
    (net (code "85") (name "Net-(K11-Pad10)") (class "Default")
      (node (ref "K11") (pin "10") (pinfunction "10_10") (pintype "passive"))
      (node (ref "K11") (pin "9") (pinfunction "9_9") (pintype "passive"))
      (node (ref "K7") (pin "11") (pinfunction "11_11") (pintype "passive"))
      (node (ref "K7") (pin "12") (pinfunction "12_12") (pintype "passive"))
      (node (ref "K8") (pin "11") (pinfunction "11_11") (pintype "passive"))
      (node (ref "K8") (pin "12") (pinfunction "12_12") (pintype "passive"))
    )
    (net (code "86") (name "Net-(K11-Pad11)") (class "Default")
      (node (ref "K11") (pin "11") (pinfunction "11_11") (pintype "passive"))
      (node (ref "K11") (pin "12") (pinfunction "12_12") (pintype "passive"))
      (node (ref "K13") (pin "10") (pinfunction "10_10") (pintype "passive"))
      (node (ref "K13") (pin "9") (pinfunction "9_9") (pintype "passive"))
      (node (ref "K9") (pin "11") (pinfunction "11_11") (pintype "passive"))
      (node (ref "K9") (pin "12") (pinfunction "12_12") (pintype "passive"))
    )
    (net (code "87") (name "Net-(K11-Pad13)") (class "Default")
      (node (ref "K11") (pin "13") (pinfunction "13_13") (pintype "passive"))
      (node (ref "K11") (pin "14") (pinfunction "14_14") (pintype "passive"))
      (node (ref "K14") (pin "10") (pinfunction "10_10") (pintype "passive"))
      (node (ref "K14") (pin "9") (pinfunction "9_9") (pintype "passive"))
      (node (ref "K9") (pin "13") (pinfunction "13_13") (pintype "passive"))
      (node (ref "K9") (pin "14") (pinfunction "14_14") (pintype "passive"))
    )
    (net (code "88") (name "Net-(K12-Pad7)") (class "Default")
      (node (ref "K12") (pin "7") (pinfunction "7_7") (pintype "passive"))
      (node (ref "K12") (pin "8") (pinfunction "8_8") (pintype "passive"))
      (node (ref "K7") (pin "3") (pinfunction "3_3") (pintype "passive"))
      (node (ref "K7") (pin "4") (pinfunction "4_4") (pintype "passive"))
      (node (ref "K8") (pin "3") (pinfunction "3_3") (pintype "passive"))
      (node (ref "K8") (pin "4") (pinfunction "4_4") (pintype "passive"))
    )
    (net (code "89") (name "Net-(K12-Pad10)") (class "Default")
      (node (ref "K12") (pin "10") (pinfunction "10_10") (pintype "passive"))
      (node (ref "K12") (pin "9") (pinfunction "9_9") (pintype "passive"))
      (node (ref "K7") (pin "13") (pinfunction "13_13") (pintype "passive"))
      (node (ref "K7") (pin "14") (pinfunction "14_14") (pintype "passive"))
      (node (ref "K8") (pin "13") (pinfunction "13_13") (pintype "passive"))
      (node (ref "K8") (pin "14") (pinfunction "14_14") (pintype "passive"))
    )
    (net (code "90") (name "Net-(K13-Pad3)") (class "Default")
      (node (ref "K13") (pin "3") (pinfunction "3_3") (pintype "passive"))
      (node (ref "K13") (pin "4") (pinfunction "4_4") (pintype "passive"))
      (node (ref "K22") (pin "7") (pinfunction "7_7") (pintype "passive"))
      (node (ref "K22") (pin "8") (pinfunction "8_8") (pintype "passive"))
    )
    (net (code "91") (name "Net-(K13-Pad5)") (class "Default")
      (node (ref "K13") (pin "5") (pinfunction "5_5") (pintype "passive"))
      (node (ref "K13") (pin "6") (pinfunction "6_6") (pintype "passive"))
      (node (ref "K19") (pin "7") (pinfunction "7_7") (pintype "passive"))
      (node (ref "K19") (pin "8") (pinfunction "8_8") (pintype "passive"))
    )
    (net (code "92") (name "Net-(K13-Pad11)") (class "Default")
      (node (ref "K13") (pin "11") (pinfunction "11_11") (pintype "passive"))
      (node (ref "K13") (pin "12") (pinfunction "12_12") (pintype "passive"))
      (node (ref "K19") (pin "10") (pinfunction "10_10") (pintype "passive"))
      (node (ref "K19") (pin "9") (pinfunction "9_9") (pintype "passive"))
    )
    (net (code "93") (name "Net-(K13-Pad13)") (class "Default")
      (node (ref "K13") (pin "13") (pinfunction "13_13") (pintype "passive"))
      (node (ref "K13") (pin "14") (pinfunction "14_14") (pintype "passive"))
      (node (ref "K22") (pin "10") (pinfunction "10_10") (pintype "passive"))
      (node (ref "K22") (pin "9") (pinfunction "9_9") (pintype "passive"))
    )
    (net (code "94") (name "Net-(K14-Pad3)") (class "Default")
      (node (ref "K14") (pin "3") (pinfunction "3_3") (pintype "passive"))
      (node (ref "K14") (pin "4") (pinfunction "4_4") (pintype "passive"))
      (node (ref "K23") (pin "7") (pinfunction "7_7") (pintype "passive"))
      (node (ref "K23") (pin "8") (pinfunction "8_8") (pintype "passive"))
    )
    (net (code "95") (name "Net-(K14-Pad5)") (class "Default")
      (node (ref "K14") (pin "5") (pinfunction "5_5") (pintype "passive"))
      (node (ref "K14") (pin "6") (pinfunction "6_6") (pintype "passive"))
      (node (ref "K17") (pin "7") (pinfunction "7_7") (pintype "passive"))
      (node (ref "K17") (pin "8") (pinfunction "8_8") (pintype "passive"))
    )
    (net (code "96") (name "Net-(K14-Pad11)") (class "Default")
      (node (ref "K14") (pin "11") (pinfunction "11_11") (pintype "passive"))
      (node (ref "K14") (pin "12") (pinfunction "12_12") (pintype "passive"))
      (node (ref "K17") (pin "10") (pinfunction "10_10") (pintype "passive"))
      (node (ref "K17") (pin "9") (pinfunction "9_9") (pintype "passive"))
    )
    (net (code "97") (name "Net-(K14-Pad13)") (class "Default")
      (node (ref "K14") (pin "13") (pinfunction "13_13") (pintype "passive"))
      (node (ref "K14") (pin "14") (pinfunction "14_14") (pintype "passive"))
      (node (ref "K23") (pin "10") (pinfunction "10_10") (pintype "passive"))
      (node (ref "K23") (pin "9") (pinfunction "9_9") (pintype "passive"))
    )
    (net (code "98") (name "Net-(K15-Pad3)") (class "Default")
      (node (ref "K15") (pin "3") (pinfunction "3_3") (pintype "passive"))
      (node (ref "K15") (pin "4") (pinfunction "4_4") (pintype "passive"))
      (node (ref "K24") (pin "7") (pinfunction "7_7") (pintype "passive"))
      (node (ref "K24") (pin "8") (pinfunction "8_8") (pintype "passive"))
    )
    (net (code "99") (name "Net-(K15-Pad5)") (class "Default")
      (node (ref "K15") (pin "5") (pinfunction "5_5") (pintype "passive"))
      (node (ref "K15") (pin "6") (pinfunction "6_6") (pintype "passive"))
      (node (ref "K20") (pin "7") (pinfunction "7_7") (pintype "passive"))
      (node (ref "K20") (pin "8") (pinfunction "8_8") (pintype "passive"))
    )
    (net (code "100") (name "Net-(K15-Pad11)") (class "Default")
      (node (ref "K15") (pin "11") (pinfunction "11_11") (pintype "passive"))
      (node (ref "K15") (pin "12") (pinfunction "12_12") (pintype "passive"))
      (node (ref "K20") (pin "10") (pinfunction "10_10") (pintype "passive"))
      (node (ref "K20") (pin "9") (pinfunction "9_9") (pintype "passive"))
    )
    (net (code "101") (name "Net-(K15-Pad13)") (class "Default")
      (node (ref "K15") (pin "13") (pinfunction "13_13") (pintype "passive"))
      (node (ref "K15") (pin "14") (pinfunction "14_14") (pintype "passive"))
      (node (ref "K24") (pin "10") (pinfunction "10_10") (pintype "passive"))
      (node (ref "K24") (pin "9") (pinfunction "9_9") (pintype "passive"))
    )
    (net (code "102") (name "Net-(K16-Pad3)") (class "Default")
      (node (ref "K16") (pin "3") (pinfunction "3_3") (pintype "passive"))
      (node (ref "K16") (pin "4") (pinfunction "4_4") (pintype "passive"))
      (node (ref "K21") (pin "7") (pinfunction "7_7") (pintype "passive"))
      (node (ref "K21") (pin "8") (pinfunction "8_8") (pintype "passive"))
    )
    (net (code "103") (name "Net-(K16-Pad5)") (class "Default")
      (node (ref "K16") (pin "5") (pinfunction "5_5") (pintype "passive"))
      (node (ref "K16") (pin "6") (pinfunction "6_6") (pintype "passive"))
      (node (ref "K18") (pin "7") (pinfunction "7_7") (pintype "passive"))
      (node (ref "K18") (pin "8") (pinfunction "8_8") (pintype "passive"))
    )
    (net (code "104") (name "Net-(K16-Pad11)") (class "Default")
      (node (ref "K16") (pin "11") (pinfunction "11_11") (pintype "passive"))
      (node (ref "K16") (pin "12") (pinfunction "12_12") (pintype "passive"))
      (node (ref "K18") (pin "10") (pinfunction "10_10") (pintype "passive"))
      (node (ref "K18") (pin "9") (pinfunction "9_9") (pintype "passive"))
    )
    (net (code "105") (name "Net-(K16-Pad13)") (class "Default")
      (node (ref "K16") (pin "13") (pinfunction "13_13") (pintype "passive"))
      (node (ref "K16") (pin "14") (pinfunction "14_14") (pintype "passive"))
      (node (ref "K21") (pin "10") (pinfunction "10_10") (pintype "passive"))
      (node (ref "K21") (pin "9") (pinfunction "9_9") (pintype "passive"))
    )
  )
)
